# LCD_Connector.net
KiCad netlist of a schematic drawn in Altium Designer
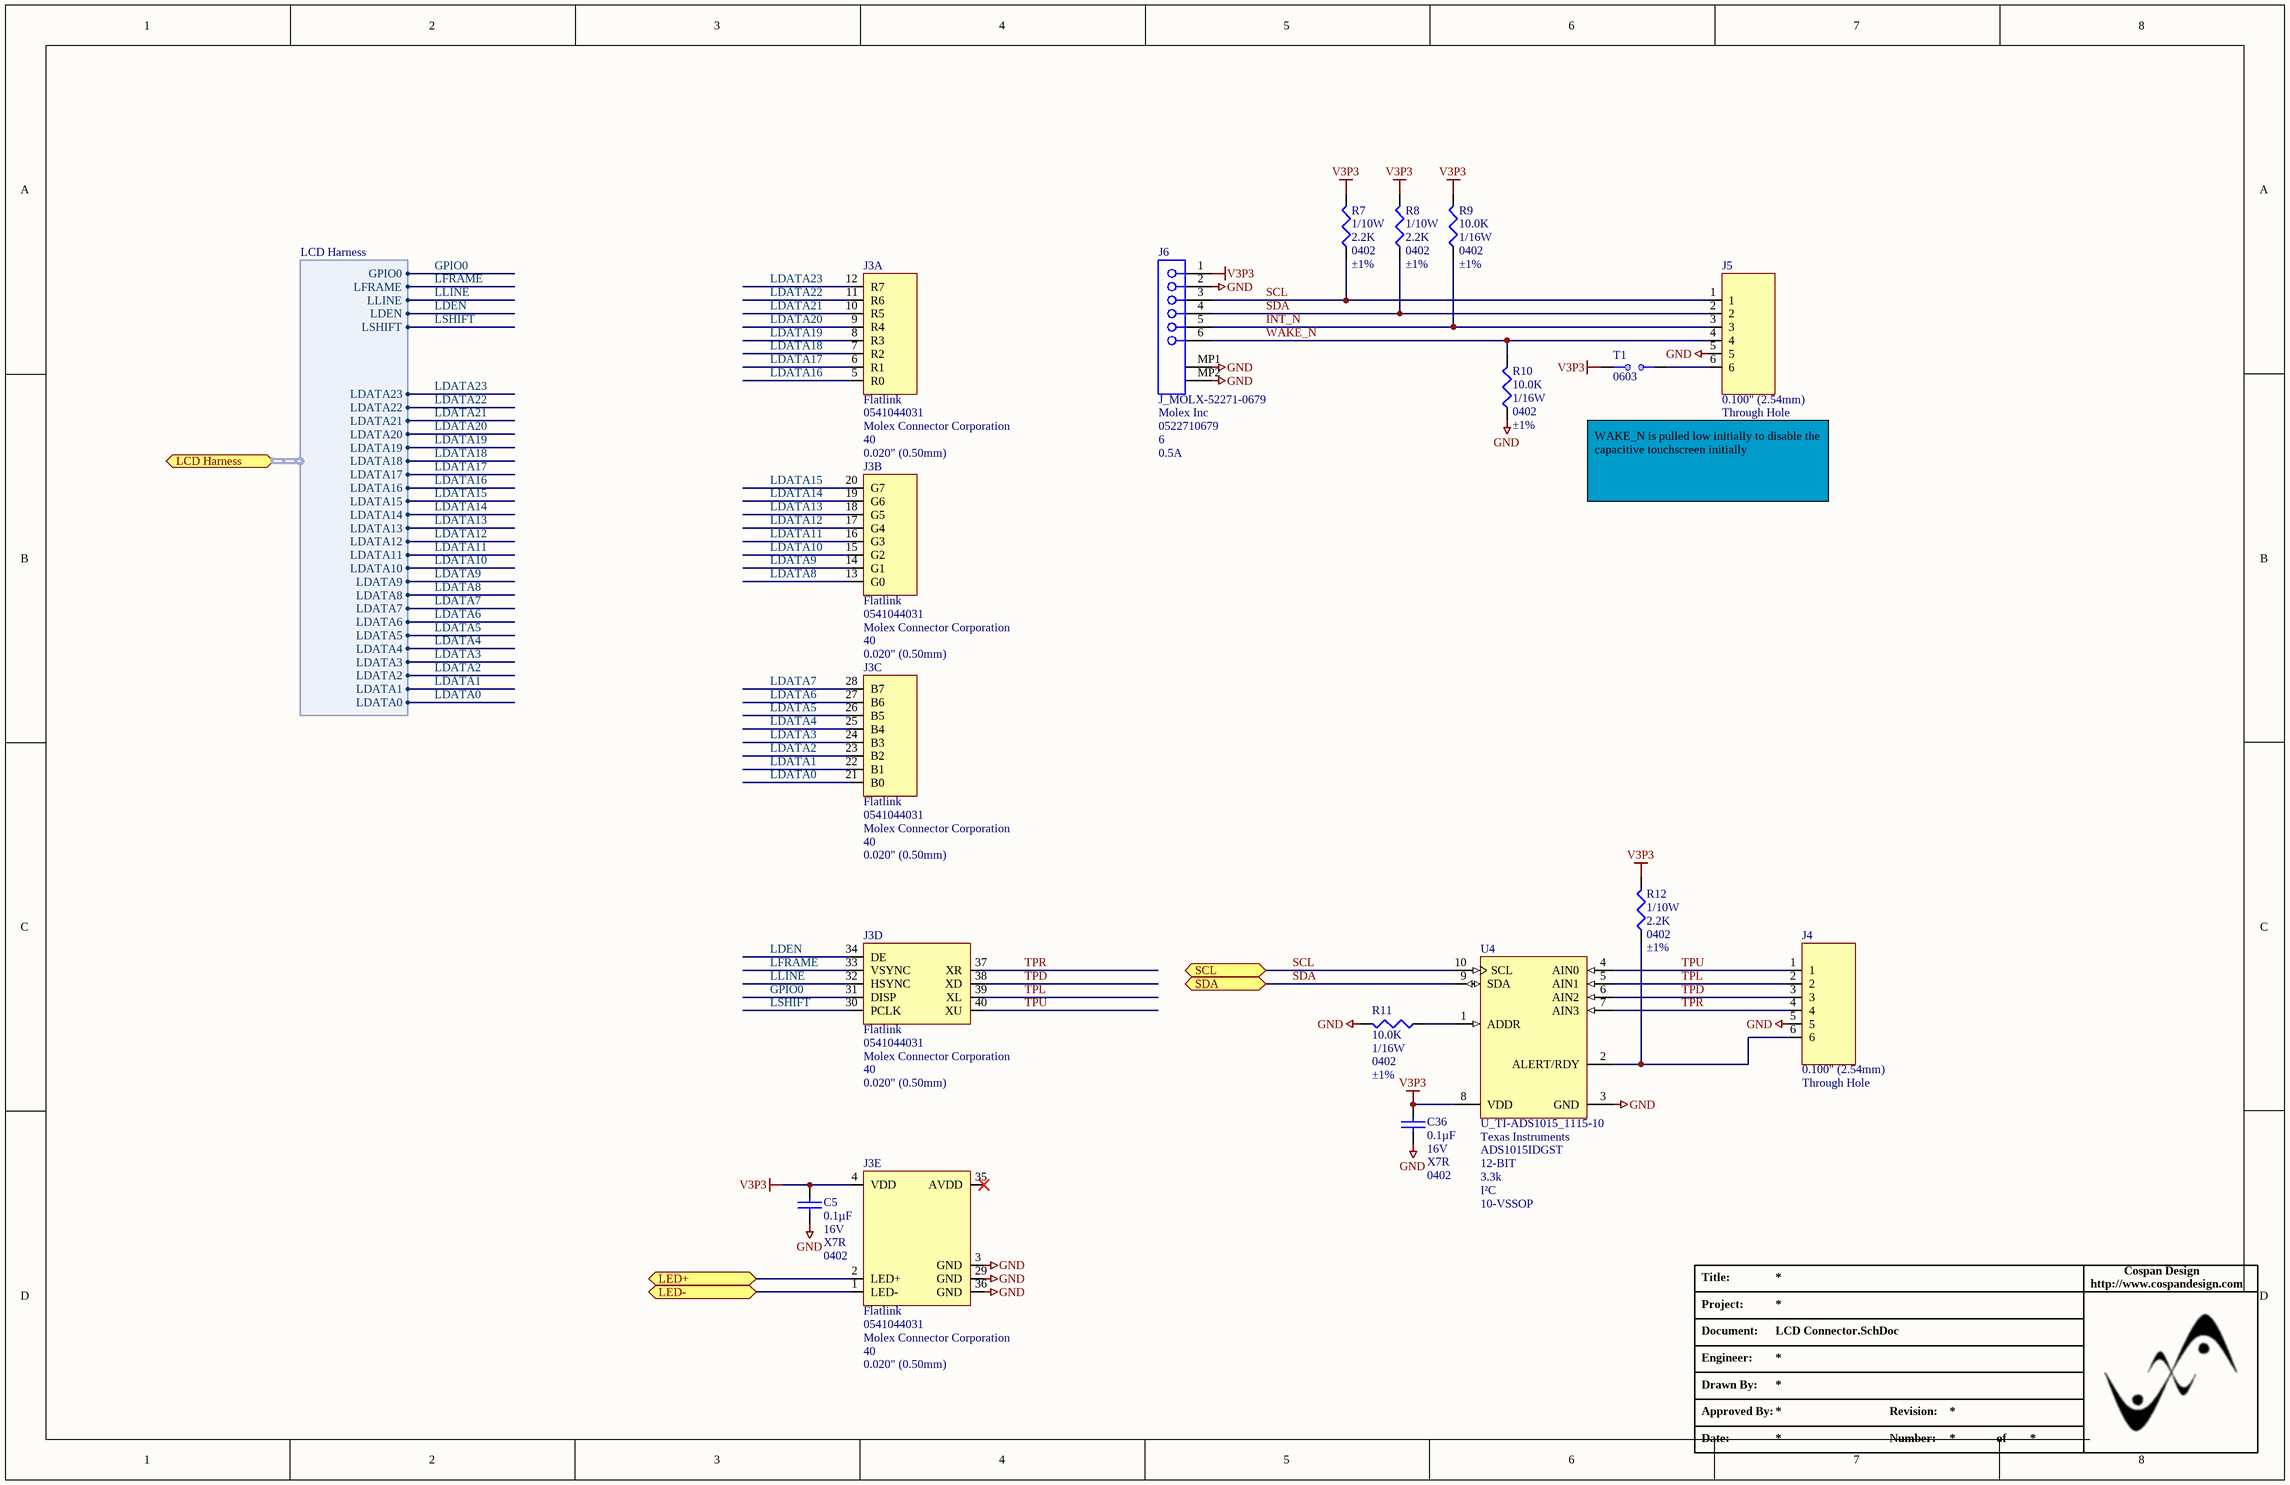
[diagram p0: LCD Connector.SchDoc]

(export (version "E")
  (design (tool "Eeschema 10.0.6"))
  (components
    (comp (ref "C5")
      (value "0.1uF")
      (footprint "C_0402")
      (description "CAP CER .10UF 16V X7R 0402")
      (fields
        (field (name "MANUFACTURER") "TDK Corporation")
        (field (name "MANUFACTURER PART NUMBER") "C1005X7R1C104K")
        (field (name "CAPACITANCE") "0.1µF")
        (field (name "VOLTAGE - RATED") "16V")
        (field (name "TEMPERATURE COEFFICIENT") "X7R")
        (field (name "PACKAGE / CASE") "0402")
      )
      (libsource (lib "Main Library") (part "C_0402_0.1UF_16V"))
    )
    (comp (ref "C36")
      (value "0.1uF")
      (footprint "C_0402")
      (description "CAP CER .10UF 16V X7R 0402")
      (fields
        (field (name "MANUFACTURER") "TDK Corporation")
        (field (name "MANUFACTURER PART NUMBER") "C1005X7R1C104K")
        (field (name "CAPACITANCE") "0.1µF")
        (field (name "VOLTAGE - RATED") "16V")
        (field (name "TEMPERATURE COEFFICIENT") "X7R")
        (field (name "PACKAGE / CASE") "0402")
      )
      (libsource (lib "Main Library") (part "C_0402_0.1UF_16V"))
    )
    (comp (ref "J3")
      (value "Flatlink")
      (footprint "FPC_40PIN")
      (description "CONN FFC/FPC .50MM 40POS R/A SMD")
      (fields
        (field (name "MANUFACTURER PART NUMBER") "0541044031")
        (field (name "MANUFACTURER") "Molex Connector Corporation")
        (field (name "NUMBER OF POSITIONS") "40")
        (field (name "PITCH") "0.020\" (0.50mm)")
      )
      (libsource (lib "Main LibraryX") (part "J_FPC_MOLEX_40POS_TOP"))
    )
    (comp (ref "J4")
      (value "J_HDR1X6_THRHOLE_VERT_FEMALE")
      (footprint "HDR_1X6 - FEMALE")
      (description "CONN HEADER FEMALE 6POS .1\" TIN")
      (fields
        (field (name "MANUFACTURER") "Samtec")
        (field (name "MANUFACTURER PART NUMBER") "SSW-106-01-T-S")
        (field (name "PITCH") "0.100\" (2.54mm)")
        (field (name "MOUNTING TYPE") "Through Hole")
      )
      (libsource (lib "Main Library") (part "J_HDR1X6_THRHOLE_VERT_FEMALE"))
    )
    (comp (ref "J5")
      (value "J_HDR1X6_THRHOLE_VERT")
      (footprint "HDR_1X6")
      (description "CONN HEADER .100\" 12POS TIN PCB")
      (fields
        (field (name "MANUFACTURER") "Samtec")
        (field (name "MANUFACTURER PART NUMBER") "TSW-106-07-T-S")
        (field (name "PITCH") "0.100\" (2.54mm)")
        (field (name "MOUNTING TYPE") "Through Hole")
      )
      (libsource (lib "Main Library") (part "J_HDR1X6_THRHOLE_VERT"))
    )
    (comp (ref "J6")
      (value "J_MOLX-52271-0679")
      (footprint "MOLX-52271-0679")
      (description "CONN FFC 6POS 1MM R/A ZIF SMD")
      (fields
        (field (name "MANUFACTURER") "Molex Inc")
        (field (name "MANUFACTURER PART NUMBER") "0522710679")
        (field (name "NUMBER OF POSITIONS") "6")
        (field (name "CURRENT RATING") "0.5A")
      )
      (libsource (lib "Main Library") (part "J_MOLX-52271-0679"))
    )
    (comp (ref "R7")
      (value "2.2k Ohms")
      (footprint "R_0402")
      (description "RES 2.20K OHM 1/10W 1% 0402 SMD")
      (fields
        (field (name "MANUFACTURER") "Yageo")
        (field (name "MANUFACTURER PART NUMBER") "RC0402FR-072K2L")
        (field (name "POWER (WATTS)") "1/10W")
        (field (name "RESISTANCE IN OHMS") "2.2K")
        (field (name "CASE") "0402")
        (field (name "TOLERANCE") "±1%")
      )
      (libsource (lib "Main Library") (part "R_0402_2.2K"))
    )
    (comp (ref "R8")
      (value "2.2k Ohms")
      (footprint "R_0402")
      (description "RES 2.20K OHM 1/10W 1% 0402 SMD")
      (fields
        (field (name "MANUFACTURER") "Yageo")
        (field (name "MANUFACTURER PART NUMBER") "RC0402FR-072K2L")
        (field (name "POWER (WATTS)") "1/10W")
        (field (name "RESISTANCE IN OHMS") "2.2K")
        (field (name "CASE") "0402")
        (field (name "TOLERANCE") "±1%")
      )
      (libsource (lib "Main Library") (part "R_0402_2.2K"))
    )
    (comp (ref "R9")
      (value "R_0402_10.0K")
      (footprint "R_0402")
      (description "RES 10.0K OHM 1/16W 1% 0402 SMD")
      (fields
        (field (name "MANUFACTURER") "Stackpole Electronics Inc")
        (field (name "MANUFACTURER PART NUMBER") "RMCF0402FT10K0")
        (field (name "RESISTANCE IN OHMS") "10.0K")
        (field (name "POWER (WATTS)") "1/16W")
        (field (name "CASE") "0402")
        (field (name "TOLERANCE") "±1%")
      )
      (libsource (lib "Main Library") (part "R_0402_10.0K"))
    )
    (comp (ref "R10")
      (value "R_0402_10.0K")
      (footprint "R_0402")
      (description "RES 10.0K OHM 1/16W 1% 0402 SMD")
      (fields
        (field (name "MANUFACTURER") "Stackpole Electronics Inc")
        (field (name "MANUFACTURER PART NUMBER") "RMCF0402FT10K0")
        (field (name "RESISTANCE IN OHMS") "10.0K")
        (field (name "POWER (WATTS)") "1/16W")
        (field (name "CASE") "0402")
        (field (name "TOLERANCE") "±1%")
      )
      (libsource (lib "Main Library") (part "R_0402_10.0K"))
    )
    (comp (ref "R11")
      (value "R_0402_10.0K")
      (footprint "R_0402")
      (description "RES 10.0K OHM 1/16W 1% 0402 SMD")
      (fields
        (field (name "MANUFACTURER") "Stackpole Electronics Inc")
        (field (name "MANUFACTURER PART NUMBER") "RMCF0402FT10K0")
        (field (name "RESISTANCE IN OHMS") "10.0K")
        (field (name "POWER (WATTS)") "1/16W")
        (field (name "CASE") "0402")
        (field (name "TOLERANCE") "±1%")
      )
      (libsource (lib "Main Library") (part "R_0402_10.0K"))
    )
    (comp (ref "R12")
      (value "2.2k Ohms")
      (footprint "R_0402")
      (description "RES 2.20K OHM 1/10W 1% 0402 SMD")
      (fields
        (field (name "MANUFACTURER") "Yageo")
        (field (name "MANUFACTURER PART NUMBER") "RC0402FR-072K2L")
        (field (name "POWER (WATTS)") "1/10W")
        (field (name "RESISTANCE IN OHMS") "2.2K")
        (field (name "CASE") "0402")
        (field (name "TOLERANCE") "±1%")
      )
      (libsource (lib "Main Library") (part "R_0402_2.2K"))
    )
    (comp (ref "T1")
      (value "Place Solder Bridge to Enable")
      (footprint "ERA-0603-SOLDER_JUMPER")
      (description "SOLDER_JUMPER PAD")
      (fields (field (name "CASE") "0603"))
      (libsource (lib "Main Library") (part "T_0603_JUMPER_PAD"))
    )
    (comp (ref "U4")
      (value "U_TI-ADS1015_1115-10")
      (footprint "TI-DGS10_L")
      (description "IC ADC 12BIT I2C W/REF 10-MSOP")
      (fields
        (field (name "MANUFACTURER") "Texas Instruments")
        (field (name "MANUFACTURER PART NUMBER") "ADS1015IDGST")
        (field (name "NUMBER OF BITS") "12-BIT")
        (field (name "SAMPLING RATE (PER SECOND)") "3.3k")
        (field (name "DATA INTERFACE") "I²C")
        (field (name "SUPPLIER DEVICE PACKAGE") "10-VSSOP")
      )
      (libsource (lib "Main LibraryX") (part "U_TI-ADS1015_1115-10"))
    )
  )
  (nets
    (net (code "3") (name "/GPIO0") (class "Default")
      (node (ref "J3") (pin "31") (pinfunction "DISP_31") (pintype "passive"))
    )
    (net (code "4") (name "/INT_N") (class "Default")
      (node (ref "J5") (pin "3") (pinfunction "3_3") (pintype "passive"))
      (node (ref "J6") (pin "5") (pinfunction "5_5") (pintype "passive"))
      (node (ref "R9") (pin "2") (pinfunction "2_2") (pintype "passive"))
    )
    (net (code "5") (name "/LDATA0") (class "Default")
      (node (ref "J3") (pin "21") (pinfunction "B0_21") (pintype "passive"))
    )
    (net (code "6") (name "/LDATA1") (class "Default")
      (node (ref "J3") (pin "22") (pinfunction "B1_22") (pintype "passive"))
    )
    (net (code "7") (name "/LDATA2") (class "Default")
      (node (ref "J3") (pin "23") (pinfunction "B2_23") (pintype "passive"))
    )
    (net (code "8") (name "/LDATA3") (class "Default")
      (node (ref "J3") (pin "24") (pinfunction "B3_24") (pintype "passive"))
    )
    (net (code "9") (name "/LDATA4") (class "Default")
      (node (ref "J3") (pin "25") (pinfunction "B4_25") (pintype "passive"))
    )
    (net (code "10") (name "/LDATA5") (class "Default")
      (node (ref "J3") (pin "26") (pinfunction "B5_26") (pintype "passive"))
    )
    (net (code "11") (name "/LDATA6") (class "Default")
      (node (ref "J3") (pin "27") (pinfunction "B6_27") (pintype "passive"))
    )
    (net (code "12") (name "/LDATA7") (class "Default")
      (node (ref "J3") (pin "28") (pinfunction "B7_28") (pintype "passive"))
    )
    (net (code "13") (name "/LDATA8") (class "Default")
      (node (ref "J3") (pin "13") (pinfunction "G0_13") (pintype "passive"))
    )
    (net (code "14") (name "/LDATA9") (class "Default")
      (node (ref "J3") (pin "14") (pinfunction "G1_14") (pintype "passive"))
    )
    (net (code "15") (name "/LDATA10") (class "Default")
      (node (ref "J3") (pin "15") (pinfunction "G2_15") (pintype "passive"))
    )
    (net (code "16") (name "/LDATA11") (class "Default")
      (node (ref "J3") (pin "16") (pinfunction "G3_16") (pintype "passive"))
    )
    (net (code "17") (name "/LDATA12") (class "Default")
      (node (ref "J3") (pin "17") (pinfunction "G4_17") (pintype "passive"))
    )
    (net (code "18") (name "/LDATA13") (class "Default")
      (node (ref "J3") (pin "18") (pinfunction "G5_18") (pintype "passive"))
    )
    (net (code "19") (name "/LDATA14") (class "Default")
      (node (ref "J3") (pin "19") (pinfunction "G6_19") (pintype "passive"))
    )
    (net (code "20") (name "/LDATA15") (class "Default")
      (node (ref "J3") (pin "20") (pinfunction "G7_20") (pintype "passive"))
    )
    (net (code "21") (name "/LDATA16") (class "Default")
      (node (ref "J3") (pin "5") (pinfunction "R0_5") (pintype "passive"))
    )
    (net (code "22") (name "/LDATA17") (class "Default")
      (node (ref "J3") (pin "6") (pinfunction "R1_6") (pintype "passive"))
    )
    (net (code "23") (name "/LDATA18") (class "Default")
      (node (ref "J3") (pin "7") (pinfunction "R2_7") (pintype "passive"))
    )
    (net (code "24") (name "/LDATA19") (class "Default")
      (node (ref "J3") (pin "8") (pinfunction "R3_8") (pintype "passive"))
    )
    (net (code "25") (name "/LDATA20") (class "Default")
      (node (ref "J3") (pin "9") (pinfunction "R4_9") (pintype "passive"))
    )
    (net (code "26") (name "/LDATA21") (class "Default")
      (node (ref "J3") (pin "10") (pinfunction "R5_10") (pintype "passive"))
    )
    (net (code "27") (name "/LDATA22") (class "Default")
      (node (ref "J3") (pin "11") (pinfunction "R6_11") (pintype "passive"))
    )
    (net (code "28") (name "/LDATA23") (class "Default")
      (node (ref "J3") (pin "12") (pinfunction "R7_12") (pintype "passive"))
    )
    (net (code "29") (name "/LDEN") (class "Default")
      (node (ref "J3") (pin "34") (pinfunction "DE_34") (pintype "passive"))
    )
    (net (code "30") (name "/LED+") (class "Default")
      (node (ref "J3") (pin "2") (pinfunction "LED+_2") (pintype "passive"))
    )
    (net (code "31") (name "/LED-") (class "Default")
      (node (ref "J3") (pin "1") (pinfunction "LED-_1") (pintype "passive"))
    )
    (net (code "32") (name "/LFRAME") (class "Default")
      (node (ref "J3") (pin "33") (pinfunction "VSYNC_33") (pintype "passive"))
    )
    (net (code "33") (name "/LLINE") (class "Default")
      (node (ref "J3") (pin "32") (pinfunction "HSYNC_32") (pintype "passive"))
    )
    (net (code "34") (name "/LSHIFT") (class "Default")
      (node (ref "J3") (pin "30") (pinfunction "PCLK_30") (pintype "passive"))
    )
    (net (code "35") (name "/SCL") (class "Default")
      (node (ref "J5") (pin "1") (pinfunction "1_1") (pintype "passive"))
      (node (ref "J6") (pin "3") (pinfunction "3_3") (pintype "passive"))
      (node (ref "R7") (pin "2") (pinfunction "2_2") (pintype "passive"))
      (node (ref "U4") (pin "10") (pinfunction "SCL_10") (pintype "input"))
    )
    (net (code "36") (name "/SDA") (class "Default")
      (node (ref "J5") (pin "2") (pinfunction "2_2") (pintype "passive"))
      (node (ref "J6") (pin "4") (pinfunction "4_4") (pintype "passive"))
      (node (ref "R8") (pin "2") (pinfunction "2_2") (pintype "passive"))
      (node (ref "U4") (pin "9") (pinfunction "SDA_9") (pintype "bidirectional"))
    )
    (net (code "37") (name "/TPD") (class "Default")
      (node (ref "J3") (pin "38") (pinfunction "XD_38") (pintype "passive"))
      (node (ref "J4") (pin "3") (pinfunction "3_3") (pintype "passive"))
      (node (ref "U4") (pin "6") (pinfunction "AIN2_6") (pintype "input"))
    )
    (net (code "38") (name "/TPL") (class "Default")
      (node (ref "J3") (pin "39") (pinfunction "XL_39") (pintype "passive"))
      (node (ref "J4") (pin "2") (pinfunction "2_2") (pintype "passive"))
      (node (ref "U4") (pin "5") (pinfunction "AIN1_5") (pintype "input"))
    )
    (net (code "39") (name "/TPR") (class "Default")
      (node (ref "J3") (pin "37") (pinfunction "XR_37") (pintype "passive"))
      (node (ref "J4") (pin "4") (pinfunction "4_4") (pintype "passive"))
      (node (ref "U4") (pin "7") (pinfunction "AIN3_7") (pintype "input"))
    )
    (net (code "40") (name "/TPU") (class "Default")
      (node (ref "J3") (pin "40") (pinfunction "XU_40") (pintype "passive"))
      (node (ref "J4") (pin "1") (pinfunction "1_1") (pintype "passive"))
      (node (ref "U4") (pin "4") (pinfunction "AIN0_4") (pintype "input"))
    )
    (net (code "41") (name "/WAKE_N") (class "Default")
      (node (ref "J5") (pin "4") (pinfunction "4_4") (pintype "passive"))
      (node (ref "J6") (pin "6") (pinfunction "6_6") (pintype "passive"))
      (node (ref "R10") (pin "1") (pinfunction "1_1") (pintype "passive"))
    )
    (net (code "43") (name "GND") (class "Default")
      (node (ref "C36") (pin "1") (pinfunction "1_1") (pintype "passive"))
      (node (ref "C5") (pin "1") (pinfunction "1_1") (pintype "passive"))
      (node (ref "J3") (pin "29") (pinfunction "GND_29") (pintype "passive"))
      (node (ref "J3") (pin "3") (pinfunction "GND_3") (pintype "passive"))
      (node (ref "J3") (pin "36") (pinfunction "GND_36") (pintype "passive"))
      (node (ref "J4") (pin "5") (pinfunction "5_5") (pintype "passive"))
      (node (ref "J5") (pin "5") (pinfunction "5_5") (pintype "passive"))
      (node (ref "J6") (pin "2") (pinfunction "2_2") (pintype "passive"))
      (node (ref "J6") (pin "MP1") (pinfunction "MP1_MP1") (pintype "passive"))
      (node (ref "J6") (pin "MP2") (pinfunction "MP2_MP2") (pintype "passive"))
      (node (ref "R10") (pin "2") (pinfunction "2_2") (pintype "passive"))
      (node (ref "R11") (pin "1") (pinfunction "1_1") (pintype "passive"))
      (node (ref "U4") (pin "3") (pinfunction "GND_3") (pintype "power_in"))
    )
    (net (code "44") (name "Net-(J5-Pad6)") (class "Default")
      (node (ref "J5") (pin "6") (pinfunction "6_6") (pintype "passive"))
      (node (ref "T1") (pin "2") (pinfunction "2_2") (pintype "passive"))
    )
    (net (code "45") (name "Net-(U4-ADDR)") (class "Default")
      (node (ref "R11") (pin "2") (pinfunction "2_2") (pintype "passive"))
      (node (ref "U4") (pin "1") (pinfunction "ADDR_1") (pintype "input"))
    )
    (net (code "46") (name "Net-(U4-ALERT{slash}RDY)") (class "Default")
      (node (ref "J4") (pin "6") (pinfunction "6_6") (pintype "passive"))
      (node (ref "R12") (pin "2") (pinfunction "2_2") (pintype "passive"))
      (node (ref "U4") (pin "2") (pinfunction "ALERT/RDY_2") (pintype "open_collector"))
    )
    (net (code "47") (name "V3P3") (class "Default")
      (node (ref "C36") (pin "2") (pinfunction "2_2") (pintype "passive"))
      (node (ref "C5") (pin "2") (pinfunction "2_2") (pintype "passive"))
      (node (ref "J3") (pin "4") (pinfunction "VDD_4") (pintype "passive"))
      (node (ref "J6") (pin "1") (pinfunction "1_1") (pintype "passive"))
      (node (ref "R12") (pin "1") (pinfunction "1_1") (pintype "passive"))
      (node (ref "R7") (pin "1") (pinfunction "1_1") (pintype "passive"))
      (node (ref "R8") (pin "1") (pinfunction "1_1") (pintype "passive"))
      (node (ref "R9") (pin "1") (pinfunction "1_1") (pintype "passive"))
      (node (ref "T1") (pin "1") (pinfunction "1_1") (pintype "passive"))
      (node (ref "U4") (pin "8") (pinfunction "VDD_8") (pintype "power_in"))
    )
    (net (code "48") (name "unconnected-(J3E-AVDD-Pad35)") (class "Default")
      (node (ref "J3") (pin "35") (pinfunction "AVDD_35") (pintype "passive+no_connect"))
    )
  )
)
